# com.net
KiCad netlist of a schematic drawn in Altium Designer
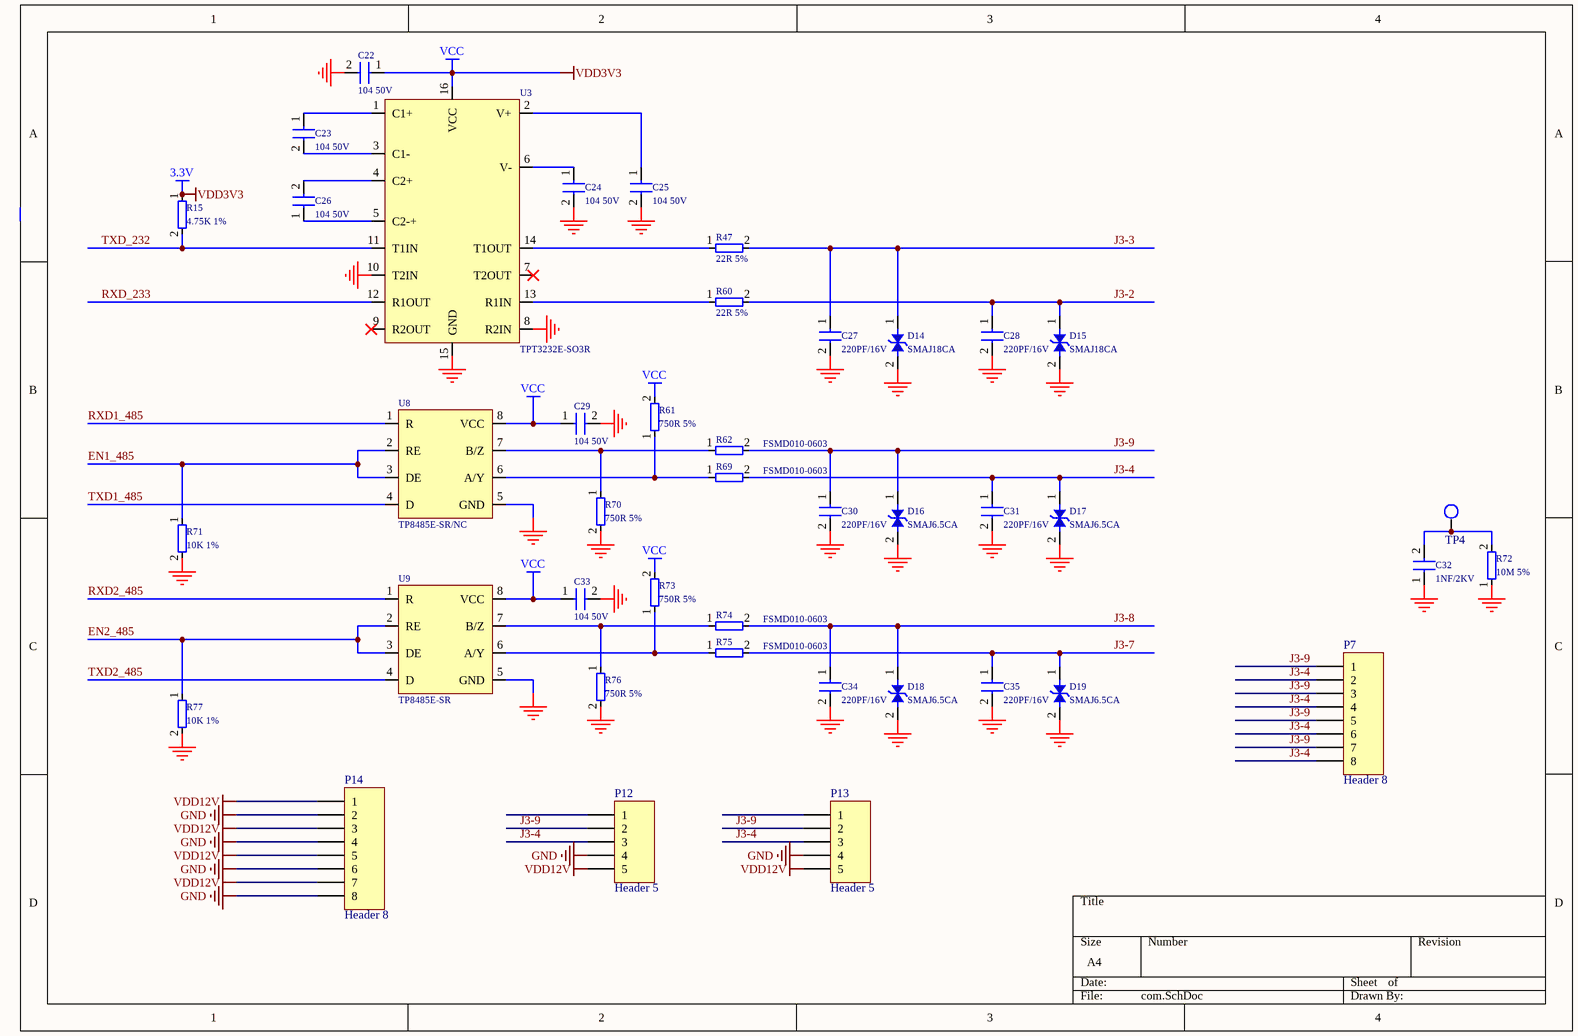
[diagram p0: com.SchDoc]

(export (version "E")
  (design (tool "Eeschema 10.0.6"))
  (components
    (comp (ref "C22") (value "104 50V") (footprint "0603C") (libsource (lib "*") (part "CAP")))
    (comp (ref "C23") (value "104 50V") (footprint "0603C") (libsource (lib "*") (part "CAP")))
    (comp (ref "C24") (value "104 50V") (footprint "0603C") (libsource (lib "*") (part "CAP")))
    (comp (ref "C25") (value "104 50V") (footprint "0603C") (libsource (lib "*") (part "CAP")))
    (comp (ref "C26") (value "104 50V") (footprint "0603C") (libsource (lib "*") (part "CAP")))
    (comp (ref "C27") (value "220PF/16V") (footprint "0603C") (libsource (lib "*") (part "CAP")))
    (comp (ref "C28") (value "220PF/16V") (footprint "0603C") (libsource (lib "*") (part "CAP")))
    (comp (ref "C29") (value "104 50V") (footprint "0603C") (libsource (lib "*") (part "CAP")))
    (comp (ref "C30") (value "220PF/16V") (footprint "0603C") (libsource (lib "*") (part "CAP")))
    (comp (ref "C31") (value "220PF/16V") (footprint "0603C") (libsource (lib "*") (part "CAP")))
    (comp (ref "C32") (value "1NF/2KV") (footprint "1206C") (libsource (lib "*") (part "CAP")))
    (comp (ref "C33") (value "104 50V") (footprint "0603C") (libsource (lib "*") (part "CAP")))
    (comp (ref "C34") (value "220PF/16V") (footprint "0603C") (libsource (lib "*") (part "CAP")))
    (comp (ref "C35") (value "220PF/16V") (footprint "0603C") (libsource (lib "*") (part "CAP")))
    (comp (ref "D14") (value "SMAJ18CA") (footprint "SMA") (libsource (lib "*") (part "D_ESD")))
    (comp (ref "D15") (value "SMAJ18CA") (footprint "SMA") (libsource (lib "*") (part "D_ESD")))
    (comp (ref "D16") (value "SMAJ6.5CA") (footprint "SMA") (libsource (lib "*") (part "D_ESD")))
    (comp (ref "D17") (value "SMAJ6.5CA") (footprint "SMA") (libsource (lib "*") (part "D_ESD")))
    (comp (ref "D18") (value "SMAJ6.5CA") (footprint "SMA") (libsource (lib "*") (part "D_ESD")))
    (comp (ref "D19") (value "SMAJ6.5CA") (footprint "SMA") (libsource (lib "*") (part "D_ESD")))
    (comp (ref "P7")
      (value "Header 8")
      (footprint "8X2.54MMZ")
      (description "Header, 8-Pin")
      (fields (field (name "PUBLISHER") "Altium Limited"))
      (libsource (lib "Miscellaneous Connectors") (part "Header 8"))
    )
    (comp (ref "P12")
      (value "Header 5")
      (footprint "5X2.54MMZ")
      (description "Header, 5-Pin")
      (fields (field (name "PUBLISHER") "Altium Limited"))
      (libsource (lib "Miscellaneous Connectors") (part "Header 5"))
    )
    (comp (ref "P13")
      (value "Header 5")
      (footprint "5X2.54MMZ")
      (description "Header, 5-Pin")
      (fields (field (name "PUBLISHER") "Altium Limited"))
      (libsource (lib "Miscellaneous Connectors") (part "Header 5"))
    )
    (comp (ref "P14")
      (value "Header 8")
      (footprint "电解模块主控板_V1.1_ZM_202109181:8X2.54MMZ")
      (description "Header, 8-Pin")
      (fields (field (name "PUBLISHER") "Altium Limited"))
      (libsource (lib "Miscellaneous Connectors") (part "Header 8"))
    )
    (comp (ref "R15") (value "4.75K 1%") (footprint "0603R") (libsource (lib "*") (part "RES")))
    (comp (ref "R47") (value "22R 5%") (footprint "0603R") (libsource (lib "*") (part "RES")))
    (comp (ref "R60") (value "22R 5%") (footprint "0603R") (libsource (lib "*") (part "RES")))
    (comp (ref "R61") (value "750R 5%") (footprint "0603R") (libsource (lib "*") (part "RES")))
    (comp (ref "R62") (value "FSMD010-0603") (footprint "0603R") (libsource (lib "*") (part "RES")))
    (comp (ref "R69") (value "FSMD010-0603") (footprint "0603R") (libsource (lib "*") (part "RES")))
    (comp (ref "R70") (value "750R 5%") (footprint "0603R") (libsource (lib "*") (part "RES")))
    (comp (ref "R71") (value "10K 1%") (footprint "0603R") (libsource (lib "*") (part "RES")))
    (comp (ref "R72") (value "10M 5%") (footprint "1206r") (libsource (lib "*") (part "RES")))
    (comp (ref "R73") (value "750R 5%") (footprint "0603R") (libsource (lib "*") (part "RES")))
    (comp (ref "R74") (value "FSMD010-0603") (footprint "0603R") (libsource (lib "*") (part "RES")))
    (comp (ref "R75") (value "FSMD010-0603") (footprint "0603R") (libsource (lib "*") (part "RES")))
    (comp (ref "R76") (value "750R 5%") (footprint "0603R") (libsource (lib "*") (part "RES")))
    (comp (ref "R77") (value "10K 1%") (footprint "0603R") (libsource (lib "*") (part "RES")))
    (comp (ref "TP4") (value "TPS") (footprint "tpd") (libsource (lib "stm32") (part "TPS")))
    (comp (ref "U3")
      (value "TPT3232E-SO3R")
      (footprint "SO-16Z")
      (libsource (lib "*") (part "TPT3232E-SO3R"))
    )
    (comp (ref "U8") (value "TP8485E-SR/NC") (footprint "SO-8") (libsource (lib "*") (part "TP8485E-SR")))
    (comp (ref "U9") (value "TP8485E-SR") (footprint "SO-8") (libsource (lib "*") (part "TP8485E-SR")))
  )
  (nets
    (net (code "1") (name "/EN1_485") (class "Default")
      (node (ref "R71") (pin "1") (pinfunction "1_1") (pintype "passive"))
      (node (ref "U8") (pin "2") (pinfunction "RE_2") (pintype "passive"))
      (node (ref "U8") (pin "3") (pinfunction "DE_3") (pintype "passive"))
    )
    (net (code "2") (name "/EN2_485") (class "Default")
      (node (ref "R77") (pin "1") (pinfunction "1_1") (pintype "passive"))
      (node (ref "U9") (pin "2") (pinfunction "RE_2") (pintype "passive"))
      (node (ref "U9") (pin "3") (pinfunction "DE_3") (pintype "passive"))
    )
    (net (code "3") (name "/J3-2") (class "Default")
      (node (ref "C28") (pin "1") (pintype "passive"))
      (node (ref "D15") (pin "1") (pintype "passive"))
      (node (ref "R60") (pin "2") (pinfunction "2_2") (pintype "passive"))
    )
    (net (code "4") (name "/J3-3") (class "Default")
      (node (ref "C27") (pin "1") (pintype "passive"))
      (node (ref "D14") (pin "1") (pintype "passive"))
      (node (ref "R47") (pin "2") (pinfunction "2_2") (pintype "passive"))
    )
    (net (code "5") (name "/J3-4") (class "Default")
      (node (ref "C31") (pin "1") (pintype "passive"))
      (node (ref "D17") (pin "1") (pintype "passive"))
      (node (ref "P12") (pin "3") (pinfunction "3_3") (pintype "passive"))
      (node (ref "P13") (pin "3") (pinfunction "3_3") (pintype "passive"))
      (node (ref "P7") (pin "2") (pinfunction "2_2") (pintype "passive"))
      (node (ref "P7") (pin "4") (pinfunction "4_4") (pintype "passive"))
      (node (ref "P7") (pin "6") (pinfunction "6_6") (pintype "passive"))
      (node (ref "P7") (pin "8") (pinfunction "8_8") (pintype "passive"))
      (node (ref "R69") (pin "2") (pinfunction "2_2") (pintype "passive"))
    )
    (net (code "6") (name "/J3-7") (class "Default")
      (node (ref "C35") (pin "1") (pintype "passive"))
      (node (ref "D19") (pin "1") (pintype "passive"))
      (node (ref "R75") (pin "2") (pinfunction "2_2") (pintype "passive"))
    )
    (net (code "7") (name "/J3-8") (class "Default")
      (node (ref "C34") (pin "1") (pintype "passive"))
      (node (ref "D18") (pin "1") (pintype "passive"))
      (node (ref "R74") (pin "2") (pinfunction "2_2") (pintype "passive"))
    )
    (net (code "8") (name "/J3-9") (class "Default")
      (node (ref "C30") (pin "1") (pintype "passive"))
      (node (ref "D16") (pin "1") (pintype "passive"))
      (node (ref "P12") (pin "2") (pinfunction "2_2") (pintype "passive"))
      (node (ref "P13") (pin "2") (pinfunction "2_2") (pintype "passive"))
      (node (ref "P7") (pin "1") (pinfunction "1_1") (pintype "passive"))
      (node (ref "P7") (pin "3") (pinfunction "3_3") (pintype "passive"))
      (node (ref "P7") (pin "5") (pinfunction "5_5") (pintype "passive"))
      (node (ref "P7") (pin "7") (pinfunction "7_7") (pintype "passive"))
      (node (ref "R62") (pin "2") (pinfunction "2_2") (pintype "passive"))
    )
    (net (code "9") (name "/RXD1_485") (class "Default")
      (node (ref "U8") (pin "1") (pinfunction "R_1") (pintype "passive"))
    )
    (net (code "10") (name "/RXD2_485") (class "Default")
      (node (ref "U9") (pin "1") (pinfunction "R_1") (pintype "passive"))
    )
    (net (code "11") (name "/RXD_233") (class "Default")
      (node (ref "U3") (pin "12") (pinfunction "R1OUT_12") (pintype "passive"))
    )
    (net (code "12") (name "/TXD1_485") (class "Default")
      (node (ref "U8") (pin "4") (pinfunction "D_4") (pintype "passive"))
    )
    (net (code "13") (name "/TXD2_485") (class "Default")
      (node (ref "U9") (pin "4") (pinfunction "D_4") (pintype "passive"))
    )
    (net (code "14") (name "/TXD_232") (class "Default")
      (node (ref "R15") (pin "2") (pinfunction "2_2") (pintype "passive"))
      (node (ref "U3") (pin "11") (pinfunction "T1IN_11") (pintype "passive"))
    )
    (net (code "15") (name "3.3V") (class "Default")
      (node (ref "C22") (pin "1") (pintype "passive"))
      (node (ref "C29") (pin "1") (pintype "passive"))
      (node (ref "C33") (pin "1") (pintype "passive"))
      (node (ref "R15") (pin "1") (pinfunction "1_1") (pintype "passive"))
      (node (ref "R61") (pin "2") (pinfunction "2_2") (pintype "passive"))
      (node (ref "R73") (pin "2") (pinfunction "2_2") (pintype "passive"))
      (node (ref "U3") (pin "16") (pinfunction "VCC_16") (pintype "passive"))
      (node (ref "U8") (pin "8") (pinfunction "VCC_8") (pintype "passive"))
      (node (ref "U9") (pin "8") (pinfunction "VCC_8") (pintype "passive"))
    )
    (net (code "16") (name "GND") (class "Default")
      (node (ref "C22") (pin "2") (pintype "passive"))
      (node (ref "C24") (pin "2") (pintype "passive"))
      (node (ref "C25") (pin "2") (pintype "passive"))
      (node (ref "C27") (pin "2") (pintype "passive"))
      (node (ref "C28") (pin "2") (pintype "passive"))
      (node (ref "C29") (pin "2") (pintype "passive"))
      (node (ref "C30") (pin "2") (pintype "passive"))
      (node (ref "C31") (pin "2") (pintype "passive"))
      (node (ref "C32") (pin "1") (pintype "passive"))
      (node (ref "C33") (pin "2") (pintype "passive"))
      (node (ref "C34") (pin "2") (pintype "passive"))
      (node (ref "C35") (pin "2") (pintype "passive"))
      (node (ref "D14") (pin "2") (pintype "passive"))
      (node (ref "D15") (pin "2") (pintype "passive"))
      (node (ref "D16") (pin "2") (pintype "passive"))
      (node (ref "D17") (pin "2") (pintype "passive"))
      (node (ref "D18") (pin "2") (pintype "passive"))
      (node (ref "D19") (pin "2") (pintype "passive"))
      (node (ref "P12") (pin "4") (pinfunction "4_4") (pintype "passive"))
      (node (ref "P13") (pin "4") (pinfunction "4_4") (pintype "passive"))
      (node (ref "P14") (pin "2") (pinfunction "2_2") (pintype "passive"))
      (node (ref "P14") (pin "4") (pinfunction "4_4") (pintype "passive"))
      (node (ref "P14") (pin "6") (pinfunction "6_6") (pintype "passive"))
      (node (ref "P14") (pin "8") (pinfunction "8_8") (pintype "passive"))
      (node (ref "R70") (pin "2") (pinfunction "2_2") (pintype "passive"))
      (node (ref "R71") (pin "2") (pinfunction "2_2") (pintype "passive"))
      (node (ref "R72") (pin "1") (pinfunction "1_1") (pintype "passive"))
      (node (ref "R76") (pin "2") (pinfunction "2_2") (pintype "passive"))
      (node (ref "R77") (pin "2") (pinfunction "2_2") (pintype "passive"))
      (node (ref "U3") (pin "10") (pinfunction "T2IN_10") (pintype "passive"))
      (node (ref "U3") (pin "15") (pinfunction "GND_15") (pintype "passive"))
      (node (ref "U3") (pin "8") (pinfunction "R2IN_8") (pintype "passive"))
      (node (ref "U8") (pin "5") (pinfunction "GND_5") (pintype "passive"))
      (node (ref "U9") (pin "5") (pinfunction "GND_5") (pintype "passive"))
    )
    (net (code "17") (name "Net-(C32-Pad2)") (class "Default")
      (node (ref "C32") (pin "2") (pintype "passive"))
      (node (ref "R72") (pin "2") (pinfunction "2_2") (pintype "passive"))
      (node (ref "TP4") (pin "1") (pinfunction "1_1") (pintype "passive"))
    )
    (net (code "18") (name "Net-(U3-C1+)") (class "Default")
      (node (ref "C23") (pin "1") (pintype "passive"))
      (node (ref "U3") (pin "1") (pinfunction "C1+_1") (pintype "passive"))
    )
    (net (code "19") (name "Net-(U3-C1-)") (class "Default")
      (node (ref "C23") (pin "2") (pintype "passive"))
      (node (ref "U3") (pin "3") (pinfunction "C1-_3") (pintype "passive"))
    )
    (net (code "20") (name "Net-(U3-C2+)") (class "Default")
      (node (ref "C26") (pin "2") (pintype "passive"))
      (node (ref "U3") (pin "4") (pinfunction "C2+_4") (pintype "passive"))
    )
    (net (code "21") (name "Net-(U3-C2-+)") (class "Default")
      (node (ref "C26") (pin "1") (pintype "passive"))
      (node (ref "U3") (pin "5") (pinfunction "C2-+_5") (pintype "passive"))
    )
    (net (code "22") (name "Net-(U3-R1IN)") (class "Default")
      (node (ref "R60") (pin "1") (pinfunction "1_1") (pintype "passive"))
      (node (ref "U3") (pin "13") (pinfunction "R1IN_13") (pintype "passive"))
    )
    (net (code "23") (name "Net-(U3-T1OUT)") (class "Default")
      (node (ref "R47") (pin "1") (pinfunction "1_1") (pintype "passive"))
      (node (ref "U3") (pin "14") (pinfunction "T1OUT_14") (pintype "passive"))
    )
    (net (code "24") (name "Net-(U3-V+)") (class "Default")
      (node (ref "C25") (pin "1") (pintype "passive"))
      (node (ref "U3") (pin "2") (pinfunction "V+_2") (pintype "passive"))
    )
    (net (code "25") (name "Net-(U3-V-)") (class "Default")
      (node (ref "C24") (pin "1") (pintype "passive"))
      (node (ref "U3") (pin "6") (pinfunction "V-_6") (pintype "passive"))
    )
    (net (code "26") (name "Net-(U8-A{slash}Y)") (class "Default")
      (node (ref "R61") (pin "1") (pinfunction "1_1") (pintype "passive"))
      (node (ref "R69") (pin "1") (pinfunction "1_1") (pintype "passive"))
      (node (ref "U8") (pin "6") (pinfunction "A/Y_6") (pintype "passive"))
    )
    (net (code "27") (name "Net-(U8-B{slash}Z)") (class "Default")
      (node (ref "R62") (pin "1") (pinfunction "1_1") (pintype "passive"))
      (node (ref "R70") (pin "1") (pinfunction "1_1") (pintype "passive"))
      (node (ref "U8") (pin "7") (pinfunction "B/Z_7") (pintype "passive"))
    )
    (net (code "28") (name "Net-(U9-A{slash}Y)") (class "Default")
      (node (ref "R73") (pin "1") (pinfunction "1_1") (pintype "passive"))
      (node (ref "R75") (pin "1") (pinfunction "1_1") (pintype "passive"))
      (node (ref "U9") (pin "6") (pinfunction "A/Y_6") (pintype "passive"))
    )
    (net (code "29") (name "Net-(U9-B{slash}Z)") (class "Default")
      (node (ref "R74") (pin "1") (pinfunction "1_1") (pintype "passive"))
      (node (ref "R76") (pin "1") (pinfunction "1_1") (pintype "passive"))
      (node (ref "U9") (pin "7") (pinfunction "B/Z_7") (pintype "passive"))
    )
    (net (code "30") (name "VDD12V") (class "Default")
      (node (ref "P12") (pin "5") (pinfunction "5_5") (pintype "passive"))
      (node (ref "P13") (pin "5") (pinfunction "5_5") (pintype "passive"))
      (node (ref "P14") (pin "1") (pinfunction "1_1") (pintype "passive"))
      (node (ref "P14") (pin "3") (pinfunction "3_3") (pintype "passive"))
      (node (ref "P14") (pin "5") (pinfunction "5_5") (pintype "passive"))
      (node (ref "P14") (pin "7") (pinfunction "7_7") (pintype "passive"))
    )
    (net (code "31") (name "unconnected-(P12-Pad1)") (class "Default")
      (node (ref "P12") (pin "1") (pinfunction "1_1") (pintype "passive"))
    )
    (net (code "32") (name "unconnected-(P13-Pad1)") (class "Default")
      (node (ref "P13") (pin "1") (pinfunction "1_1") (pintype "passive"))
    )
    (net (code "33") (name "unconnected-(U3-R2OUT-Pad9)") (class "Default")
      (node (ref "U3") (pin "9") (pinfunction "R2OUT_9") (pintype "passive+no_connect"))
    )
    (net (code "34") (name "unconnected-(U3-T2OUT-Pad7)") (class "Default")
      (node (ref "U3") (pin "7") (pinfunction "T2OUT_7") (pintype "passive+no_connect"))
    )
  )
)
